# debug.net
KiCad netlist of a schematic drawn in Altium Designer
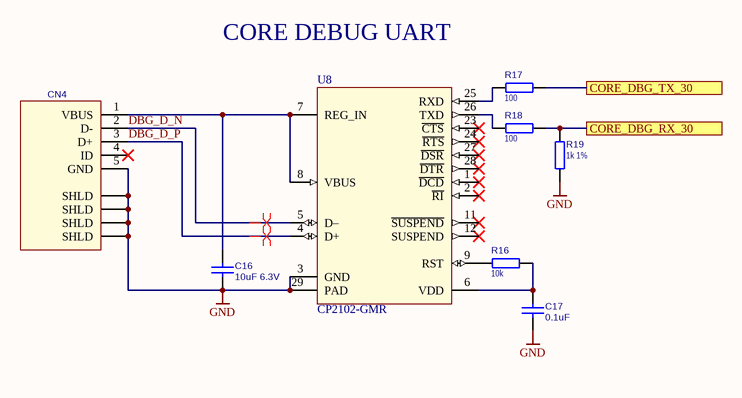
[diagram p0: debug.SchDoc]

(export (version "E")
  (design (tool "Eeschema 10.0.6"))
  (components
    (comp (ref "C16")
      (value "10uF 6.3V")
      (footprint "Capacitors:C0603")
      (description "CAP_NPOL")
      (fields (field (name "Comment") "CC0603MRX5R5BB106"))
      (libsource (lib "capacitors") (part "CAP_NPOL"))
    )
    (comp (ref "C17")
      (value "0.1uF")
      (footprint "Capacitors:C0603")
      (description "CAP_NPOL")
      (fields (field (name "Comment") "C1608X7R1H104K080AA"))
      (libsource (lib "capacitors") (part "CAP_NPOL"))
    )
    (comp (ref "CN4")
      (value "USB Type-B mini")
      (footprint "USB-B_SMD-MICRO-01")
      (libsource (lib "USB") (part "USB-B-M"))
    )
    (comp (ref "R16")
      (value "10k")
      (footprint "R0603")
      (description "RES")
      (libsource (lib "resistors") (part "RESISTOR"))
    )
    (comp (ref "R17")
      (value "100")
      (footprint "R0603")
      (description "RES")
      (libsource (lib "resistors") (part "RESISTOR"))
    )
    (comp (ref "R18")
      (value "100")
      (footprint "R0603")
      (description "RES")
      (libsource (lib "resistors") (part "RESISTOR"))
    )
    (comp (ref "R19")
      (value "1k 1%")
      (footprint "R0603")
      (description "RES")
      (libsource (lib "resistors") (part "RESISTOR"))
    )
    (comp (ref "U8")
      (value "CP2102-GMR")
      (footprint "QFN-28-4x4")
      (description "SINGLE-CHIP USB-TO-UART BRIDGE")
      (libsource (lib "CP2102") (part "CP2102"))
    )
  )
  (nets
    (net (code "1") (name "/CORE_DBG_RX_30") (class "Default")
      (node (ref "R18") (pin "1") (pinfunction "1_1") (pintype "passive"))
      (node (ref "R19") (pin "1") (pinfunction "1_1") (pintype "passive"))
    )
    (net (code "2") (name "/CORE_DBG_TX_30") (class "Default")
      (node (ref "R17") (pin "1") (pinfunction "1_1") (pintype "passive"))
    )
    (net (code "3") (name "/DBG_D_N") (class "Default")
      (node (ref "CN4") (pin "2") (pinfunction "D-_2") (pintype "passive"))
      (node (ref "U8") (pin "5") (pinfunction "D–_5") (pintype "bidirectional"))
    )
    (net (code "4") (name "/DBG_D_P") (class "Default")
      (node (ref "CN4") (pin "3") (pinfunction "D+_3") (pintype "passive"))
      (node (ref "U8") (pin "4") (pinfunction "D+_4") (pintype "bidirectional"))
    )
    (net (code "5") (name "GND") (class "Default")
      (node (ref "C16") (pin "2") (pinfunction "2_2") (pintype "passive"))
      (node (ref "C17") (pin "2") (pinfunction "2_2") (pintype "passive"))
      (node (ref "CN4") (pin "5") (pinfunction "GND_5") (pintype "passive"))
      (node (ref "CN4") (pin "6") (pinfunction "SHLD_6") (pintype "passive"))
      (node (ref "CN4") (pin "7") (pinfunction "SHLD_7") (pintype "passive"))
      (node (ref "CN4") (pin "8") (pinfunction "SHLD_8") (pintype "passive"))
      (node (ref "CN4") (pin "9") (pinfunction "SHLD_9") (pintype "passive"))
      (node (ref "R19") (pin "2") (pinfunction "2_2") (pintype "passive"))
      (node (ref "U8") (pin "29") (pinfunction "PAD_29") (pintype "passive"))
      (node (ref "U8") (pin "3") (pinfunction "GND_3") (pintype "power_in"))
    )
    (net (code "6") (name "Net-(CN4-VBUS)") (class "Default")
      (node (ref "C16") (pin "1") (pinfunction "1_1") (pintype "passive"))
      (node (ref "CN4") (pin "1") (pinfunction "VBUS_1") (pintype "passive"))
      (node (ref "U8") (pin "7") (pinfunction "REG_IN_7") (pintype "power_in"))
      (node (ref "U8") (pin "8") (pinfunction "VBUS_8") (pintype "input"))
    )
    (net (code "7") (name "Net-(U8-RST)") (class "Default")
      (node (ref "R16") (pin "2") (pinfunction "2_2") (pintype "passive"))
      (node (ref "U8") (pin "9") (pinfunction "RST_9") (pintype "bidirectional"))
    )
    (net (code "8") (name "Net-(U8-RXD)") (class "Default")
      (node (ref "R17") (pin "2") (pinfunction "2_2") (pintype "passive"))
      (node (ref "U8") (pin "25") (pinfunction "RXD_25") (pintype "input"))
    )
    (net (code "9") (name "Net-(U8-TXD)") (class "Default")
      (node (ref "R18") (pin "2") (pinfunction "2_2") (pintype "passive"))
      (node (ref "U8") (pin "26") (pinfunction "TXD_26") (pintype "output"))
    )
    (net (code "10") (name "Net-(U8-VDD)") (class "Default")
      (node (ref "C17") (pin "1") (pinfunction "1_1") (pintype "passive"))
      (node (ref "R16") (pin "1") (pinfunction "1_1") (pintype "passive"))
      (node (ref "U8") (pin "6") (pinfunction "VDD_6") (pintype "power_in"))
    )
    (net (code "11") (name "unconnected-(CN4-ID-Pad4)") (class "Default")
      (node (ref "CN4") (pin "4") (pinfunction "ID_4") (pintype "passive+no_connect"))
    )
    (net (code "12") (name "unconnected-(CN4-PadMH1)") (class "Default")
      (node (ref "CN4") (pin "MH1") (pintype "passive"))
    )
    (net (code "13") (name "unconnected-(CN4-PadMH2)") (class "Default")
      (node (ref "CN4") (pin "MH2") (pintype "passive"))
    )
    (net (code "14") (name "unconnected-(U8-SUSPEND-Pad12)") (class "Default")
      (node (ref "U8") (pin "12") (pinfunction "SUSPEND_12") (pintype "output+no_connect"))
    )
    (net (code "15") (name "unconnected-(U8-~{CTS}-Pad23)") (class "Default")
      (node (ref "U8") (pin "23") (pinfunction "~{CTS}_23") (pintype "input+no_connect"))
    )
    (net (code "16") (name "unconnected-(U8-~{DCD}-Pad1)") (class "Default")
      (node (ref "U8") (pin "1") (pinfunction "~{DCD}_1") (pintype "input+no_connect"))
    )
    (net (code "17") (name "unconnected-(U8-~{DSR}-Pad27)") (class "Default")
      (node (ref "U8") (pin "27") (pinfunction "~{DSR}_27") (pintype "input+no_connect"))
    )
    (net (code "18") (name "unconnected-(U8-~{DTR}-Pad28)") (class "Default")
      (node (ref "U8") (pin "28") (pinfunction "~{DTR}_28") (pintype "output+no_connect"))
    )
    (net (code "19") (name "unconnected-(U8-~{RI}-Pad2)") (class "Default")
      (node (ref "U8") (pin "2") (pinfunction "~{RI}_2") (pintype "input+no_connect"))
    )
    (net (code "20") (name "unconnected-(U8-~{RTS}-Pad24)") (class "Default")
      (node (ref "U8") (pin "24") (pinfunction "~{RTS}_24") (pintype "output+no_connect"))
    )
    (net (code "21") (name "unconnected-(U8-~{SUSPEND}-Pad11)") (class "Default")
      (node (ref "U8") (pin "11") (pinfunction "~{SUSPEND}_11") (pintype "output+no_connect"))
    )
  )
)
